# usb-audio01.net
KiCad netlist of a schematic drawn in EAGLE
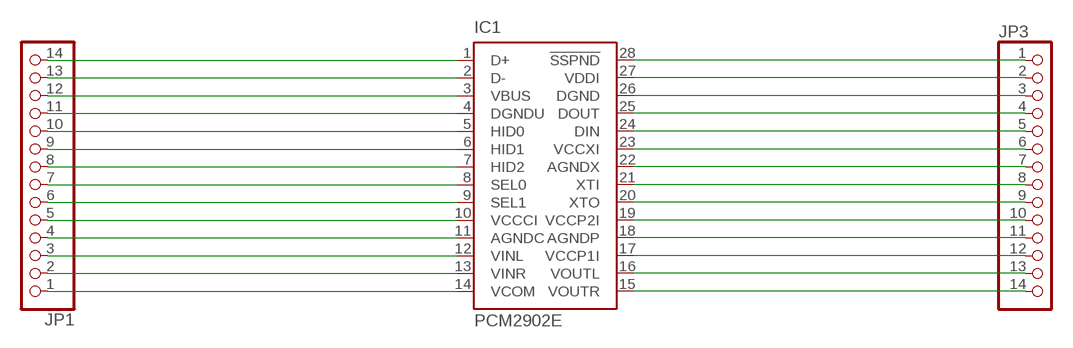
[diagram p0: schematic, sheet 1]

(export (version "E")
  (design (tool "Eeschema 10.0.6"))
  (components
    (comp (ref "IC1")
      (value "PCM2902E")
      (footprint "eagle-import:SSOP28DB")
      (fields (field (name "MF") "TEXAS INSTRUMENT CONNECTORS"))
      (libsource (lib "eagle-import") (part "PCM2902E"))
    )
    (comp (ref "JP1")
      (value "PINHD-1X14")
      (footprint "eagle-import:1X14")
      (libsource (lib "eagle-import") (part "PINHD-1X14"))
    )
    (comp (ref "JP3")
      (value "PINHD-1X14")
      (footprint "eagle-import:1X14")
      (libsource (lib "eagle-import") (part "PINHD-1X14"))
    )
  )
  (nets
    (net (code "1") (name "Net-(IC1-AGNDC)") (class "Default")
      (node (ref "IC1") (pin "11") (pinfunction "AGNDC_11") (pintype "power_in"))
      (node (ref "JP1") (pin "4") (pinfunction "4_4") (pintype "passive"))
    )
    (net (code "2") (name "Net-(IC1-AGNDP)") (class "Default")
      (node (ref "IC1") (pin "18") (pinfunction "AGNDP_18") (pintype "power_in"))
      (node (ref "JP3") (pin "11") (pinfunction "11_11") (pintype "passive"))
    )
    (net (code "3") (name "Net-(IC1-AGNDX)") (class "Default")
      (node (ref "IC1") (pin "22") (pinfunction "AGNDX_22") (pintype "power_in"))
      (node (ref "JP3") (pin "7") (pinfunction "7_7") (pintype "passive"))
    )
    (net (code "4") (name "Net-(IC1-D+)") (class "Default")
      (node (ref "IC1") (pin "1") (pinfunction "D+_1") (pintype "bidirectional"))
      (node (ref "JP1") (pin "14") (pinfunction "14_14") (pintype "passive"))
    )
    (net (code "5") (name "Net-(IC1-D-)") (class "Default")
      (node (ref "IC1") (pin "2") (pinfunction "D-_2") (pintype "bidirectional"))
      (node (ref "JP1") (pin "13") (pinfunction "13_13") (pintype "passive"))
    )
    (net (code "6") (name "Net-(IC1-DGND)") (class "Default")
      (node (ref "IC1") (pin "26") (pinfunction "DGND_26") (pintype "power_in"))
      (node (ref "JP3") (pin "3") (pinfunction "3_3") (pintype "passive"))
    )
    (net (code "7") (name "Net-(IC1-DGNDU)") (class "Default")
      (node (ref "IC1") (pin "4") (pinfunction "DGNDU_4") (pintype "power_in"))
      (node (ref "JP1") (pin "11") (pinfunction "11_11") (pintype "passive"))
    )
    (net (code "8") (name "Net-(IC1-DIN)") (class "Default")
      (node (ref "IC1") (pin "24") (pinfunction "DIN_24") (pintype "input"))
      (node (ref "JP3") (pin "5") (pinfunction "5_5") (pintype "passive"))
    )
    (net (code "9") (name "Net-(IC1-DOUT)") (class "Default")
      (node (ref "IC1") (pin "25") (pinfunction "DOUT_25") (pintype "output"))
      (node (ref "JP3") (pin "4") (pinfunction "4_4") (pintype "passive"))
    )
    (net (code "10") (name "Net-(IC1-HID0)") (class "Default")
      (node (ref "IC1") (pin "5") (pinfunction "HID0_5") (pintype "input"))
      (node (ref "JP1") (pin "10") (pinfunction "10_10") (pintype "passive"))
    )
    (net (code "11") (name "Net-(IC1-HID1)") (class "Default")
      (node (ref "IC1") (pin "6") (pinfunction "HID1_6") (pintype "input"))
      (node (ref "JP1") (pin "9") (pinfunction "9_9") (pintype "passive"))
    )
    (net (code "12") (name "Net-(IC1-HID2)") (class "Default")
      (node (ref "IC1") (pin "7") (pinfunction "HID2_7") (pintype "input"))
      (node (ref "JP1") (pin "8") (pinfunction "8_8") (pintype "passive"))
    )
    (net (code "13") (name "Net-(IC1-SEL0)") (class "Default")
      (node (ref "IC1") (pin "8") (pinfunction "SEL0_8") (pintype "input"))
      (node (ref "JP1") (pin "7") (pinfunction "7_7") (pintype "passive"))
    )
    (net (code "14") (name "Net-(IC1-SEL1)") (class "Default")
      (node (ref "IC1") (pin "9") (pinfunction "SEL1_9") (pintype "input"))
      (node (ref "JP1") (pin "6") (pinfunction "6_6") (pintype "passive"))
    )
    (net (code "15") (name "Net-(IC1-VBUS)") (class "Default")
      (node (ref "IC1") (pin "3") (pinfunction "VBUS_3") (pintype "power_in"))
      (node (ref "JP1") (pin "12") (pinfunction "12_12") (pintype "passive"))
    )
    (net (code "16") (name "Net-(IC1-VCCCI)") (class "Default")
      (node (ref "IC1") (pin "10") (pinfunction "VCCCI_10") (pintype "power_in"))
      (node (ref "JP1") (pin "5") (pinfunction "5_5") (pintype "passive"))
    )
    (net (code "17") (name "Net-(IC1-VCCP1I)") (class "Default")
      (node (ref "IC1") (pin "17") (pinfunction "VCCP1I_17") (pintype "input"))
      (node (ref "JP3") (pin "12") (pinfunction "12_12") (pintype "passive"))
    )
    (net (code "18") (name "Net-(IC1-VCCP2I)") (class "Default")
      (node (ref "IC1") (pin "19") (pinfunction "VCCP2I_19") (pintype "power_in"))
      (node (ref "JP3") (pin "10") (pinfunction "10_10") (pintype "passive"))
    )
    (net (code "19") (name "Net-(IC1-VCCXI)") (class "Default")
      (node (ref "IC1") (pin "23") (pinfunction "VCCXI_23") (pintype "power_in"))
      (node (ref "JP3") (pin "6") (pinfunction "6_6") (pintype "passive"))
    )
    (net (code "20") (name "Net-(IC1-VCOM)") (class "Default")
      (node (ref "IC1") (pin "14") (pinfunction "VCOM_14") (pintype "power_in"))
      (node (ref "JP1") (pin "1") (pinfunction "1_1") (pintype "passive"))
    )
    (net (code "21") (name "Net-(IC1-VDDI)") (class "Default")
      (node (ref "IC1") (pin "27") (pinfunction "VDDI_27") (pintype "power_in"))
      (node (ref "JP3") (pin "2") (pinfunction "2_2") (pintype "passive"))
    )
    (net (code "22") (name "Net-(IC1-VINL)") (class "Default")
      (node (ref "IC1") (pin "12") (pinfunction "VINL_12") (pintype "input"))
      (node (ref "JP1") (pin "3") (pinfunction "3_3") (pintype "passive"))
    )
    (net (code "23") (name "Net-(IC1-VINR)") (class "Default")
      (node (ref "IC1") (pin "13") (pinfunction "VINR_13") (pintype "input"))
      (node (ref "JP1") (pin "2") (pinfunction "2_2") (pintype "passive"))
    )
    (net (code "24") (name "Net-(IC1-VOUTL)") (class "Default")
      (node (ref "IC1") (pin "16") (pinfunction "VOUTL_16") (pintype "output"))
      (node (ref "JP3") (pin "13") (pinfunction "13_13") (pintype "passive"))
    )
    (net (code "25") (name "Net-(IC1-VOUTR)") (class "Default")
      (node (ref "IC1") (pin "15") (pinfunction "VOUTR_15") (pintype "output"))
      (node (ref "JP3") (pin "14") (pinfunction "14_14") (pintype "passive"))
    )
    (net (code "26") (name "Net-(IC1-XTI)") (class "Default")
      (node (ref "IC1") (pin "21") (pinfunction "XTI_21") (pintype "input"))
      (node (ref "JP3") (pin "8") (pinfunction "8_8") (pintype "passive"))
    )
    (net (code "27") (name "Net-(IC1-XTO)") (class "Default")
      (node (ref "IC1") (pin "20") (pinfunction "XTO_20") (pintype "output"))
      (node (ref "JP3") (pin "9") (pinfunction "9_9") (pintype "passive"))
    )
    (net (code "28") (name "Net-(IC1-~{SSPND})") (class "Default")
      (node (ref "IC1") (pin "28") (pinfunction "~{SSPND}_28") (pintype "output"))
      (node (ref "JP3") (pin "1") (pinfunction "1_1") (pintype "passive"))
    )
  )
)
